# stm32-synthesizer_Schematic.net
KiCad netlist of a schematic drawn in Altium Designer
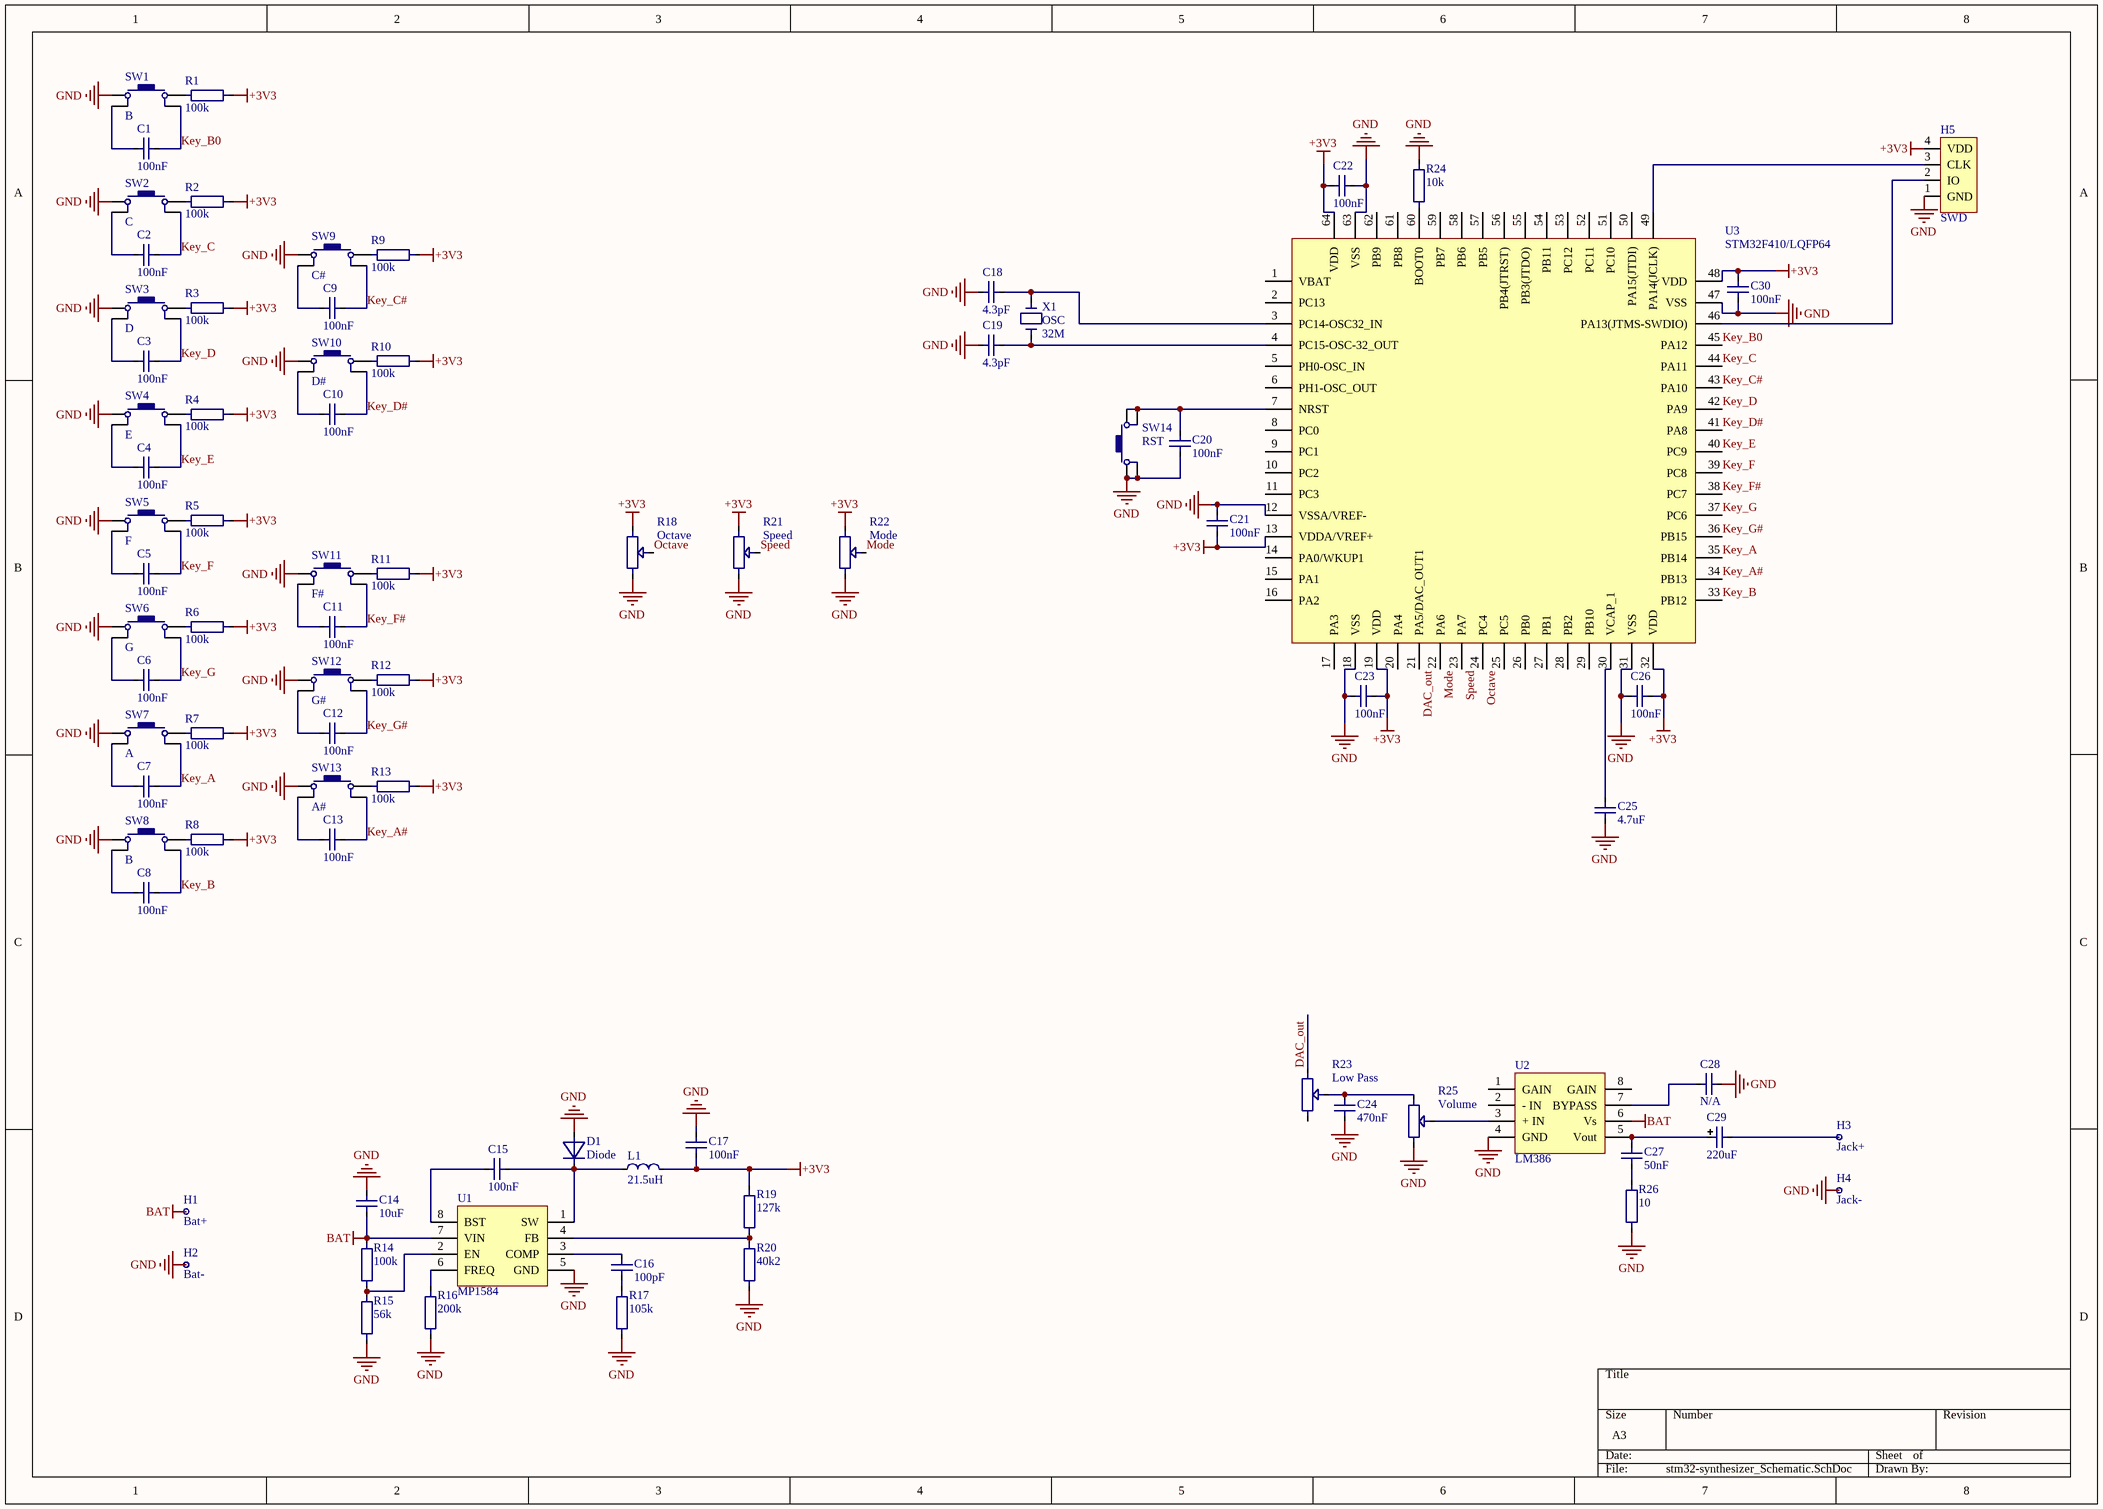
[diagram p0: stm32-synthesizer_Schematic.SchDoc]

(export (version "E")
  (design (tool "Eeschema 10.0.6"))
  (components
    (comp (ref "C1")
      (value "100nF")
      (footprint "CRCW0805")
      (libsource (lib "Schematic_Library_Warga") (part "Capacitor"))
    )
    (comp (ref "C2")
      (value "100nF")
      (footprint "CRCW0805")
      (libsource (lib "Schematic_Library_Warga") (part "Capacitor"))
    )
    (comp (ref "C3")
      (value "100nF")
      (footprint "CRCW0805")
      (libsource (lib "Schematic_Library_Warga") (part "Capacitor"))
    )
    (comp (ref "C4")
      (value "100nF")
      (footprint "CRCW0805")
      (libsource (lib "Schematic_Library_Warga") (part "Capacitor"))
    )
    (comp (ref "C5")
      (value "100nF")
      (footprint "CRCW0805")
      (libsource (lib "Schematic_Library_Warga") (part "Capacitor"))
    )
    (comp (ref "C6")
      (value "100nF")
      (footprint "CRCW0805")
      (libsource (lib "Schematic_Library_Warga") (part "Capacitor"))
    )
    (comp (ref "C7")
      (value "100nF")
      (footprint "CRCW0805")
      (libsource (lib "Schematic_Library_Warga") (part "Capacitor"))
    )
    (comp (ref "C8")
      (value "100nF")
      (footprint "CRCW0805")
      (libsource (lib "Schematic_Library_Warga") (part "Capacitor"))
    )
    (comp (ref "C9")
      (value "100nF")
      (footprint "CRCW0805")
      (libsource (lib "Schematic_Library_Warga") (part "Capacitor"))
    )
    (comp (ref "C10")
      (value "100nF")
      (footprint "CRCW0805")
      (libsource (lib "Schematic_Library_Warga") (part "Capacitor"))
    )
    (comp (ref "C11")
      (value "100nF")
      (footprint "CRCW0805")
      (libsource (lib "Schematic_Library_Warga") (part "Capacitor"))
    )
    (comp (ref "C12")
      (value "100nF")
      (footprint "CRCW0805")
      (libsource (lib "Schematic_Library_Warga") (part "Capacitor"))
    )
    (comp (ref "C13")
      (value "100nF")
      (footprint "CRCW0805")
      (libsource (lib "Schematic_Library_Warga") (part "Capacitor"))
    )
    (comp (ref "C14")
      (value "10uF")
      (footprint "CRCW0805")
      (libsource (lib "Schematic_Library_Warga") (part "Capacitor"))
    )
    (comp (ref "C15")
      (value "100nF")
      (footprint "GRM188")
      (libsource (lib "Schematic_Library_Warga") (part "Capacitor"))
    )
    (comp (ref "C16")
      (value "100pF")
      (footprint "CRCW0805")
      (libsource (lib "Schematic_Library_Warga") (part "Capacitor"))
    )
    (comp (ref "C17")
      (value "100nF")
      (footprint "GRM188")
      (libsource (lib "Schematic_Library_Warga") (part "Capacitor"))
    )
    (comp (ref "C18")
      (value "4.3pF")
      (footprint "CRCW0805")
      (libsource (lib "Schematic_Library_Warga") (part "Capacitor"))
    )
    (comp (ref "C19")
      (value "4.3pF")
      (footprint "CRCW0805")
      (libsource (lib "Schematic_Library_Warga") (part "Capacitor"))
    )
    (comp (ref "C20")
      (value "100nF")
      (footprint "CRCW0805")
      (libsource (lib "Schematic_Library_Warga") (part "Capacitor"))
    )
    (comp (ref "C21")
      (value "100nF")
      (footprint "CRCW0805")
      (libsource (lib "Schematic_Library_Warga") (part "Capacitor"))
    )
    (comp (ref "C22")
      (value "100nF")
      (footprint "CRCW0805")
      (libsource (lib "Schematic_Library_Warga") (part "Capacitor"))
    )
    (comp (ref "C23")
      (value "100nF")
      (footprint "CRCW0805")
      (libsource (lib "Schematic_Library_Warga") (part "Capacitor"))
    )
    (comp (ref "C24")
      (value "470nF")
      (footprint "CRCW0805")
      (libsource (lib "Schematic_Library_Warga") (part "Capacitor"))
    )
    (comp (ref "C25")
      (value "4.7uF")
      (footprint "CRCW0805")
      (libsource (lib "Schematic_Library_Warga") (part "Capacitor"))
    )
    (comp (ref "C26")
      (value "100nF")
      (footprint "CRCW0805")
      (libsource (lib "Schematic_Library_Warga") (part "Capacitor"))
    )
    (comp (ref "C27")
      (value "50nF")
      (footprint "CRCW0805")
      (libsource (lib "Schematic_Library_Warga") (part "Capacitor"))
    )
    (comp (ref "C28")
      (value "N/A")
      (footprint "CRCW0805")
      (libsource (lib "Schematic_Library_Warga") (part "Capacitor"))
    )
    (comp (ref "C29")
      (value "220uF")
      (footprint "CAPAE6766X81M")
      (libsource (lib "Schematic_Library_Warga") (part "Capacitor_Polarized"))
    )
    (comp (ref "C30")
      (value "100nF")
      (footprint "CRCW0805")
      (libsource (lib "Schematic_Library_Warga") (part "Capacitor"))
    )
    (comp (ref "D1")
      (value "Diode")
      (footprint "DIODES-INCORPORATED_1N5819")
      (libsource (lib "Schematic_Library_Warga") (part "Diode"))
    )
    (comp (ref "H1")
      (value "Bat+")
      (footprint "Hole 1mm")
      (libsource (lib "Schematic_Library_Warga") (part "Cable Hole"))
    )
    (comp (ref "H2")
      (value "Bat-")
      (footprint "Hole 1mm")
      (libsource (lib "Schematic_Library_Warga") (part "Cable Hole"))
    )
    (comp (ref "H3")
      (value "Jack+")
      (footprint "Hole 1mm")
      (libsource (lib "Schematic_Library_Warga") (part "Cable Hole"))
    )
    (comp (ref "H4")
      (value "Jack-")
      (footprint "Hole 1mm")
      (libsource (lib "Schematic_Library_Warga") (part "Cable Hole"))
    )
    (comp (ref "H5")
      (value "SWD")
      (footprint "M20-97704")
      (libsource (lib "Schematic_Library_Warga") (part "Header4"))
    )
    (comp (ref "L1")
      (value "21.5uH")
      (footprint "Coil 0.7mm d=7mm")
      (libsource (lib "Schematic_Library_Warga") (part "Coil"))
    )
    (comp (ref "R1")
      (value "100k")
      (footprint "CRCW0805")
      (libsource (lib "Schematic_Library_Warga") (part "Resitor"))
    )
    (comp (ref "R2")
      (value "100k")
      (footprint "CRCW0805")
      (libsource (lib "Schematic_Library_Warga") (part "Resitor"))
    )
    (comp (ref "R3")
      (value "100k")
      (footprint "CRCW0805")
      (libsource (lib "Schematic_Library_Warga") (part "Resitor"))
    )
    (comp (ref "R4")
      (value "100k")
      (footprint "CRCW0805")
      (libsource (lib "Schematic_Library_Warga") (part "Resitor"))
    )
    (comp (ref "R5")
      (value "100k")
      (footprint "CRCW0805")
      (libsource (lib "Schematic_Library_Warga") (part "Resitor"))
    )
    (comp (ref "R6")
      (value "100k")
      (footprint "CRCW0805")
      (libsource (lib "Schematic_Library_Warga") (part "Resitor"))
    )
    (comp (ref "R7")
      (value "100k")
      (footprint "CRCW0805")
      (libsource (lib "Schematic_Library_Warga") (part "Resitor"))
    )
    (comp (ref "R8")
      (value "100k")
      (footprint "CRCW0805")
      (libsource (lib "Schematic_Library_Warga") (part "Resitor"))
    )
    (comp (ref "R9")
      (value "100k")
      (footprint "CRCW0805")
      (libsource (lib "Schematic_Library_Warga") (part "Resitor"))
    )
    (comp (ref "R10")
      (value "100k")
      (footprint "CRCW0805")
      (libsource (lib "Schematic_Library_Warga") (part "Resitor"))
    )
    (comp (ref "R11")
      (value "100k")
      (footprint "CRCW0805")
      (libsource (lib "Schematic_Library_Warga") (part "Resitor"))
    )
    (comp (ref "R12")
      (value "100k")
      (footprint "CRCW0805")
      (libsource (lib "Schematic_Library_Warga") (part "Resitor"))
    )
    (comp (ref "R13")
      (value "100k")
      (footprint "CRCW0805")
      (libsource (lib "Schematic_Library_Warga") (part "Resitor"))
    )
    (comp (ref "R14")
      (value "100k")
      (footprint "CRCW0805")
      (libsource (lib "Schematic_Library_Warga") (part "Resitor"))
    )
    (comp (ref "R15")
      (value "56k")
      (footprint "CRCW0805")
      (libsource (lib "Schematic_Library_Warga") (part "Resitor"))
    )
    (comp (ref "R16")
      (value "200k")
      (footprint "CRCW0805")
      (libsource (lib "Schematic_Library_Warga") (part "Resitor"))
    )
    (comp (ref "R17")
      (value "105k")
      (footprint "CRCW0805")
      (libsource (lib "Schematic_Library_Warga") (part "Resitor"))
    )
    (comp (ref "R18")
      (value "Octave")
      (footprint "RK09K113")
      (libsource (lib "Schematic_Library_Warga") (part "Potentiometer"))
    )
    (comp (ref "R19")
      (value "127k")
      (footprint "CRCW0805")
      (libsource (lib "Schematic_Library_Warga") (part "Resitor"))
    )
    (comp (ref "R20")
      (value "40k2")
      (footprint "CRCW0805")
      (libsource (lib "Schematic_Library_Warga") (part "Resitor"))
    )
    (comp (ref "R21")
      (value "Speed")
      (footprint "RK09K113")
      (libsource (lib "Schematic_Library_Warga") (part "Potentiometer"))
    )
    (comp (ref "R22")
      (value "Mode")
      (footprint "RK09K113")
      (libsource (lib "Schematic_Library_Warga") (part "Potentiometer"))
    )
    (comp (ref "R23")
      (value "Low Pass")
      (footprint "RK09K113")
      (libsource (lib "Schematic_Library_Warga") (part "Potentiometer"))
    )
    (comp (ref "R24")
      (value "10k")
      (footprint "CRCW0805")
      (libsource (lib "Schematic_Library_Warga") (part "Resitor"))
    )
    (comp (ref "R25")
      (value "Volume")
      (footprint "RK09K113")
      (libsource (lib "Schematic_Library_Warga") (part "Potentiometer"))
    )
    (comp (ref "R26")
      (value "10")
      (footprint "CRCW0805")
      (libsource (lib "Schematic_Library_Warga") (part "Resitor"))
    )
    (comp (ref "SW1")
      (value "B")
      (footprint "TL1105")
      (libsource (lib "Schematic_Library_Warga") (part "Button"))
    )
    (comp (ref "SW2")
      (value "C")
      (footprint "TL1105")
      (libsource (lib "Schematic_Library_Warga") (part "Button"))
    )
    (comp (ref "SW3")
      (value "D")
      (footprint "TL1105")
      (libsource (lib "Schematic_Library_Warga") (part "Button"))
    )
    (comp (ref "SW4")
      (value "E")
      (footprint "TL1105")
      (libsource (lib "Schematic_Library_Warga") (part "Button"))
    )
    (comp (ref "SW5")
      (value "F")
      (footprint "TL1105")
      (libsource (lib "Schematic_Library_Warga") (part "Button"))
    )
    (comp (ref "SW6")
      (value "G")
      (footprint "TL1105")
      (libsource (lib "Schematic_Library_Warga") (part "Button"))
    )
    (comp (ref "SW7")
      (value "A")
      (footprint "TL1105")
      (libsource (lib "Schematic_Library_Warga") (part "Button"))
    )
    (comp (ref "SW8")
      (value "B")
      (footprint "TL1105")
      (libsource (lib "Schematic_Library_Warga") (part "Button"))
    )
    (comp (ref "SW9")
      (value "C#")
      (footprint "TL1105")
      (libsource (lib "Schematic_Library_Warga") (part "Button"))
    )
    (comp (ref "SW10")
      (value "D#")
      (footprint "TL1105")
      (libsource (lib "Schematic_Library_Warga") (part "Button"))
    )
    (comp (ref "SW11")
      (value "F#")
      (footprint "TL1105")
      (libsource (lib "Schematic_Library_Warga") (part "Button"))
    )
    (comp (ref "SW12")
      (value "G#")
      (footprint "TL1105")
      (libsource (lib "Schematic_Library_Warga") (part "Button"))
    )
    (comp (ref "SW13")
      (value "A#")
      (footprint "TL1105")
      (libsource (lib "Schematic_Library_Warga") (part "Button"))
    )
    (comp (ref "SW14") (value "RST") (footprint "TL1105") (libsource (lib "") (part "Button_1")))
    (comp (ref "U1")
      (value "MP1584")
      (footprint "SOIC127P600X175-8N")
      (libsource (lib "Schematic_Library_Warga") (part "MP1584"))
    )
    (comp (ref "U2")
      (value "LM386")
      (footprint "LM358 SOIC")
      (description "Low Voltage Audio Power Amplifier")
      (libsource (lib "Schematic_Library_Warga") (part "LM386"))
    )
    (comp (ref "U3")
      (value "STM32F410/LQFP64")
      (footprint "STM32F410/LQFP64")
      (libsource (lib "Schematic_Library_Warga") (part "STM32F410/LQFP64"))
    )
    (comp (ref "X1")
      (value "OSC")
      (footprint "SODFL1230X430-2N")
      (fields (field (name "FREQUENCY") "32M"))
      (libsource (lib "Schematic_Library_Warga") (part "Oscillator"))
    )
  )
  (nets
    (net (code "1") (name "+3V3") (class "Default")
      (node (ref "C17") (pin "1") (pinfunction "1_1") (pintype "passive"))
      (node (ref "C21") (pin "1") (pinfunction "1_1") (pintype "passive"))
      (node (ref "C22") (pin "1") (pinfunction "1_1") (pintype "passive"))
      (node (ref "C23") (pin "1") (pinfunction "1_1") (pintype "passive"))
      (node (ref "C26") (pin "1") (pinfunction "1_1") (pintype "passive"))
      (node (ref "C30") (pin "1") (pinfunction "1_1") (pintype "passive"))
      (node (ref "H5") (pin "4") (pinfunction "VDD_4") (pintype "passive"))
      (node (ref "L1") (pin "2") (pinfunction "2_2") (pintype "passive"))
      (node (ref "R1") (pin "2") (pinfunction "2_2") (pintype "passive"))
      (node (ref "R10") (pin "2") (pinfunction "2_2") (pintype "passive"))
      (node (ref "R11") (pin "2") (pinfunction "2_2") (pintype "passive"))
      (node (ref "R12") (pin "2") (pinfunction "2_2") (pintype "passive"))
      (node (ref "R13") (pin "2") (pinfunction "2_2") (pintype "passive"))
      (node (ref "R18") (pin "1") (pinfunction "1_1") (pintype "passive"))
      (node (ref "R19") (pin "2") (pinfunction "2_2") (pintype "passive"))
      (node (ref "R2") (pin "2") (pinfunction "2_2") (pintype "passive"))
      (node (ref "R21") (pin "1") (pinfunction "1_1") (pintype "passive"))
      (node (ref "R22") (pin "1") (pinfunction "1_1") (pintype "passive"))
      (node (ref "R3") (pin "2") (pinfunction "2_2") (pintype "passive"))
      (node (ref "R4") (pin "2") (pinfunction "2_2") (pintype "passive"))
      (node (ref "R5") (pin "2") (pinfunction "2_2") (pintype "passive"))
      (node (ref "R6") (pin "2") (pinfunction "2_2") (pintype "passive"))
      (node (ref "R7") (pin "2") (pinfunction "2_2") (pintype "passive"))
      (node (ref "R8") (pin "2") (pinfunction "2_2") (pintype "passive"))
      (node (ref "R9") (pin "2") (pinfunction "2_2") (pintype "passive"))
      (node (ref "U3") (pin "13") (pinfunction "VDDA/VREF+_13") (pintype "passive"))
      (node (ref "U3") (pin "19") (pinfunction "VDD_19") (pintype "passive"))
      (node (ref "U3") (pin "32") (pinfunction "VDD_32") (pintype "passive"))
      (node (ref "U3") (pin "48") (pinfunction "VDD_48") (pintype "passive"))
      (node (ref "U3") (pin "64") (pinfunction "VDD_64") (pintype "passive"))
    )
    (net (code "2") (name "/DAC_out") (class "Default")
      (node (ref "R23") (pin "1") (pinfunction "1_1") (pintype "passive"))
      (node (ref "U3") (pin "21") (pinfunction "PA5/DAC_OUT1_21") (pintype "passive"))
    )
    (net (code "3") (name "/Key_A") (class "Default")
      (node (ref "C7") (pin "2") (pinfunction "2_2") (pintype "passive"))
      (node (ref "SW7") (pin "4") (pinfunction "4_4") (pintype "passive"))
      (node (ref "U3") (pin "35") (pinfunction "PB14_35") (pintype "passive"))
    )
    (net (code "4") (name "/Key_A#") (class "Default")
      (node (ref "C13") (pin "2") (pinfunction "2_2") (pintype "passive"))
      (node (ref "SW13") (pin "4") (pinfunction "4_4") (pintype "passive"))
      (node (ref "U3") (pin "34") (pinfunction "PB13_34") (pintype "passive"))
    )
    (net (code "5") (name "/Key_B") (class "Default")
      (node (ref "C8") (pin "2") (pinfunction "2_2") (pintype "passive"))
      (node (ref "SW8") (pin "4") (pinfunction "4_4") (pintype "passive"))
      (node (ref "U3") (pin "33") (pinfunction "PB12_33") (pintype "passive"))
    )
    (net (code "6") (name "/Key_B0") (class "Default")
      (node (ref "C1") (pin "2") (pinfunction "2_2") (pintype "passive"))
      (node (ref "SW1") (pin "4") (pinfunction "4_4") (pintype "passive"))
      (node (ref "U3") (pin "45") (pinfunction "PA12_45") (pintype "passive"))
    )
    (net (code "7") (name "/Key_C") (class "Default")
      (node (ref "C2") (pin "2") (pinfunction "2_2") (pintype "passive"))
      (node (ref "SW2") (pin "4") (pinfunction "4_4") (pintype "passive"))
      (node (ref "U3") (pin "44") (pinfunction "PA11_44") (pintype "passive"))
    )
    (net (code "8") (name "/Key_C#") (class "Default")
      (node (ref "C9") (pin "2") (pinfunction "2_2") (pintype "passive"))
      (node (ref "SW9") (pin "4") (pinfunction "4_4") (pintype "passive"))
      (node (ref "U3") (pin "43") (pinfunction "PA10_43") (pintype "passive"))
    )
    (net (code "9") (name "/Key_D") (class "Default")
      (node (ref "C3") (pin "2") (pinfunction "2_2") (pintype "passive"))
      (node (ref "SW3") (pin "4") (pinfunction "4_4") (pintype "passive"))
      (node (ref "U3") (pin "42") (pinfunction "PA9_42") (pintype "passive"))
    )
    (net (code "10") (name "/Key_D#") (class "Default")
      (node (ref "C10") (pin "2") (pinfunction "2_2") (pintype "passive"))
      (node (ref "SW10") (pin "4") (pinfunction "4_4") (pintype "passive"))
      (node (ref "U3") (pin "41") (pinfunction "PA8_41") (pintype "passive"))
    )
    (net (code "11") (name "/Key_E") (class "Default")
      (node (ref "C4") (pin "2") (pinfunction "2_2") (pintype "passive"))
      (node (ref "SW4") (pin "4") (pinfunction "4_4") (pintype "passive"))
      (node (ref "U3") (pin "40") (pinfunction "PC9_40") (pintype "passive"))
    )
    (net (code "12") (name "/Key_F") (class "Default")
      (node (ref "C5") (pin "2") (pinfunction "2_2") (pintype "passive"))
      (node (ref "SW5") (pin "4") (pinfunction "4_4") (pintype "passive"))
      (node (ref "U3") (pin "39") (pinfunction "PC8_39") (pintype "passive"))
    )
    (net (code "13") (name "/Key_F#") (class "Default")
      (node (ref "C11") (pin "2") (pinfunction "2_2") (pintype "passive"))
      (node (ref "SW11") (pin "4") (pinfunction "4_4") (pintype "passive"))
      (node (ref "U3") (pin "38") (pinfunction "PC7_38") (pintype "passive"))
    )
    (net (code "14") (name "/Key_G") (class "Default")
      (node (ref "C6") (pin "2") (pinfunction "2_2") (pintype "passive"))
      (node (ref "SW6") (pin "4") (pinfunction "4_4") (pintype "passive"))
      (node (ref "U3") (pin "37") (pinfunction "PC6_37") (pintype "passive"))
    )
    (net (code "15") (name "/Key_G#") (class "Default")
      (node (ref "C12") (pin "2") (pinfunction "2_2") (pintype "passive"))
      (node (ref "SW12") (pin "4") (pinfunction "4_4") (pintype "passive"))
      (node (ref "U3") (pin "36") (pinfunction "PB15_36") (pintype "passive"))
    )
    (net (code "16") (name "/Mode") (class "Default")
      (node (ref "R22") (pin "2") (pinfunction "2_2") (pintype "passive"))
      (node (ref "U3") (pin "22") (pinfunction "PA6_22") (pintype "passive"))
    )
    (net (code "17") (name "/Octave") (class "Default")
      (node (ref "R18") (pin "2") (pinfunction "2_2") (pintype "passive"))
      (node (ref "U3") (pin "24") (pinfunction "PC4_24") (pintype "passive"))
    )
    (net (code "18") (name "/Speed") (class "Default")
      (node (ref "R21") (pin "2") (pinfunction "2_2") (pintype "passive"))
      (node (ref "U3") (pin "23") (pinfunction "PA7_23") (pintype "passive"))
    )
    (net (code "19") (name "BAT") (class "Default")
      (node (ref "C14") (pin "1") (pinfunction "1_1") (pintype "passive"))
      (node (ref "H1") (pin "1") (pinfunction "1_1") (pintype "passive"))
      (node (ref "R14") (pin "2") (pinfunction "2_2") (pintype "passive"))
      (node (ref "U1") (pin "7") (pinfunction "VIN_7") (pintype "passive"))
      (node (ref "U2") (pin "6") (pinfunction "Vs_6") (pintype "passive"))
    )
    (net (code "20") (name "GND") (class "Default")
      (node (ref "C14") (pin "2") (pinfunction "2_2") (pintype "passive"))
      (node (ref "C17") (pin "2") (pinfunction "2_2") (pintype "passive"))
      (node (ref "C18") (pin "2") (pinfunction "2_2") (pintype "passive"))
      (node (ref "C19") (pin "2") (pinfunction "2_2") (pintype "passive"))
      (node (ref "C20") (pin "1") (pinfunction "1_1") (pintype "passive"))
      (node (ref "C21") (pin "2") (pinfunction "2_2") (pintype "passive"))
      (node (ref "C22") (pin "2") (pinfunction "2_2") (pintype "passive"))
      (node (ref "C23") (pin "2") (pinfunction "2_2") (pintype "passive"))
      (node (ref "C24") (pin "1") (pinfunction "1_1") (pintype "passive"))
      (node (ref "C25") (pin "1") (pinfunction "1_1") (pintype "passive"))
      (node (ref "C26") (pin "2") (pinfunction "2_2") (pintype "passive"))
      (node (ref "C28") (pin "2") (pinfunction "2_2") (pintype "passive"))
      (node (ref "C30") (pin "2") (pinfunction "2_2") (pintype "passive"))
      (node (ref "D1") (pin "1") (pinfunction "1_1") (pintype "passive"))
      (node (ref "H2") (pin "1") (pinfunction "1_1") (pintype "passive"))
      (node (ref "H4") (pin "1") (pinfunction "1_1") (pintype "passive"))
      (node (ref "H5") (pin "1") (pinfunction "GND_1") (pintype "passive"))
      (node (ref "R15") (pin "1") (pinfunction "1_1") (pintype "passive"))
      (node (ref "R16") (pin "1") (pinfunction "1_1") (pintype "passive"))
      (node (ref "R17") (pin "1") (pinfunction "1_1") (pintype "passive"))
      (node (ref "R18") (pin "3") (pinfunction "3_3") (pintype "passive"))
      (node (ref "R20") (pin "1") (pinfunction "1_1") (pintype "passive"))
      (node (ref "R21") (pin "3") (pinfunction "3_3") (pintype "passive"))
      (node (ref "R22") (pin "3") (pinfunction "3_3") (pintype "passive"))
      (node (ref "R24") (pin "2") (pinfunction "2_2") (pintype "passive"))
      (node (ref "R25") (pin "3") (pinfunction "3_3") (pintype "passive"))
      (node (ref "R26") (pin "1") (pinfunction "1_1") (pintype "passive"))
      (node (ref "SW1") (pin "1") (pinfunction "1_1") (pintype "passive"))
      (node (ref "SW10") (pin "1") (pinfunction "1_1") (pintype "passive"))
      (node (ref "SW11") (pin "1") (pinfunction "1_1") (pintype "passive"))
      (node (ref "SW12") (pin "1") (pinfunction "1_1") (pintype "passive"))
      (node (ref "SW13") (pin "1") (pinfunction "1_1") (pintype "passive"))
      (node (ref "SW14") (pin "1") (pinfunction "1_1") (pintype "passive"))
      (node (ref "SW14") (pin "2") (pinfunction "2_2") (pintype "passive"))
      (node (ref "SW2") (pin "1") (pinfunction "1_1") (pintype "passive"))
      (node (ref "SW3") (pin "1") (pinfunction "1_1") (pintype "passive"))
      (node (ref "SW4") (pin "1") (pinfunction "1_1") (pintype "passive"))
      (node (ref "SW5") (pin "1") (pinfunction "1_1") (pintype "passive"))
      (node (ref "SW6") (pin "1") (pinfunction "1_1") (pintype "passive"))
      (node (ref "SW7") (pin "1") (pinfunction "1_1") (pintype "passive"))
      (node (ref "SW8") (pin "1") (pinfunction "1_1") (pintype "passive"))
      (node (ref "SW9") (pin "1") (pinfunction "1_1") (pintype "passive"))
      (node (ref "U1") (pin "5") (pinfunction "GND_5") (pintype "passive"))
      (node (ref "U2") (pin "4") (pinfunction "GND_4") (pintype "passive"))
      (node (ref "U3") (pin "12") (pinfunction "VSSA/VREF-_12") (pintype "passive"))
      (node (ref "U3") (pin "18") (pinfunction "VSS_18") (pintype "passive"))
      (node (ref "U3") (pin "31") (pinfunction "VSS_31") (pintype "passive"))
      (node (ref "U3") (pin "47") (pinfunction "VSS_47") (pintype "passive"))
      (node (ref "U3") (pin "63") (pinfunction "VSS_63") (pintype "passive"))
    )
    (net (code "21") (name "Net-(C1-Pad1)") (class "Default")
      (node (ref "C1") (pin "1") (pinfunction "1_1") (pintype "passive"))
      (node (ref "SW1") (pin "2") (pinfunction "2_2") (pintype "passive"))
    )
    (net (code "22") (name "Net-(C2-Pad1)") (class "Default")
      (node (ref "C2") (pin "1") (pinfunction "1_1") (pintype "passive"))
      (node (ref "SW2") (pin "2") (pinfunction "2_2") (pintype "passive"))
    )
    (net (code "23") (name "Net-(C3-Pad1)") (class "Default")
      (node (ref "C3") (pin "1") (pinfunction "1_1") (pintype "passive"))
      (node (ref "SW3") (pin "2") (pinfunction "2_2") (pintype "passive"))
    )
    (net (code "24") (name "Net-(C4-Pad1)") (class "Default")
      (node (ref "C4") (pin "1") (pinfunction "1_1") (pintype "passive"))
      (node (ref "SW4") (pin "2") (pinfunction "2_2") (pintype "passive"))
    )
    (net (code "25") (name "Net-(C5-Pad1)") (class "Default")
      (node (ref "C5") (pin "1") (pinfunction "1_1") (pintype "passive"))
      (node (ref "SW5") (pin "2") (pinfunction "2_2") (pintype "passive"))
    )
    (net (code "26") (name "Net-(C6-Pad1)") (class "Default")
      (node (ref "C6") (pin "1") (pinfunction "1_1") (pintype "passive"))
      (node (ref "SW6") (pin "2") (pinfunction "2_2") (pintype "passive"))
    )
    (net (code "27") (name "Net-(C7-Pad1)") (class "Default")
      (node (ref "C7") (pin "1") (pinfunction "1_1") (pintype "passive"))
      (node (ref "SW7") (pin "2") (pinfunction "2_2") (pintype "passive"))
    )
    (net (code "28") (name "Net-(C8-Pad1)") (class "Default")
      (node (ref "C8") (pin "1") (pinfunction "1_1") (pintype "passive"))
      (node (ref "SW8") (pin "2") (pinfunction "2_2") (pintype "passive"))
    )
    (net (code "29") (name "Net-(C9-Pad1)") (class "Default")
      (node (ref "C9") (pin "1") (pinfunction "1_1") (pintype "passive"))
      (node (ref "SW9") (pin "2") (pinfunction "2_2") (pintype "passive"))
    )
    (net (code "30") (name "Net-(C10-Pad1)") (class "Default")
      (node (ref "C10") (pin "1") (pinfunction "1_1") (pintype "passive"))
      (node (ref "SW10") (pin "2") (pinfunction "2_2") (pintype "passive"))
    )
    (net (code "31") (name "Net-(C11-Pad1)") (class "Default")
      (node (ref "C11") (pin "1") (pinfunction "1_1") (pintype "passive"))
      (node (ref "SW11") (pin "2") (pinfunction "2_2") (pintype "passive"))
    )
    (net (code "32") (name "Net-(C12-Pad1)") (class "Default")
      (node (ref "C12") (pin "1") (pinfunction "1_1") (pintype "passive"))
      (node (ref "SW12") (pin "2") (pinfunction "2_2") (pintype "passive"))
    )
    (net (code "33") (name "Net-(C13-Pad1)") (class "Default")
      (node (ref "C13") (pin "1") (pinfunction "1_1") (pintype "passive"))
      (node (ref "SW13") (pin "2") (pinfunction "2_2") (pintype "passive"))
    )
    (net (code "34") (name "Net-(C16-Pad1)") (class "Default")
      (node (ref "C16") (pin "1") (pinfunction "1_1") (pintype "passive"))
      (node (ref "R17") (pin "2") (pinfunction "2_2") (pintype "passive"))
    )
    (net (code "35") (name "Net-(C24-Pad2)") (class "Default")
      (node (ref "C24") (pin "2") (pinfunction "2_2") (pintype "passive"))
      (node (ref "R23") (pin "2") (pinfunction "2_2") (pintype "passive"))
      (node (ref "R25") (pin "1") (pinfunction "1_1") (pintype "passive"))
    )
    (net (code "36") (name "Net-(C27-Pad2)") (class "Default")
      (node (ref "C27") (pin "2") (pinfunction "2_2") (pintype "passive"))
      (node (ref "R26") (pin "2") (pinfunction "2_2") (pintype "passive"))
    )
    (net (code "37") (name "Net-(C29-Pad1)") (class "Default")
      (node (ref "C29") (pin "1") (pinfunction "1_1") (pintype "passive"))
      (node (ref "H3") (pin "1") (pinfunction "1_1") (pintype "passive"))
    )
    (net (code "38") (name "Net-(H5-CLK)") (class "Default")
      (node (ref "H5") (pin "3") (pinfunction "CLK_3") (pintype "passive"))
      (node (ref "U3") (pin "49") (pinfunction "PA14(JCLK)_49") (pintype "passive"))
    )
    (net (code "39") (name "Net-(H5-IO)") (class "Default")
      (node (ref "H5") (pin "2") (pinfunction "IO_2") (pintype "passive"))
      (node (ref "U3") (pin "46") (pinfunction "PA13(JTMS-SWDIO)_46") (pintype "passive"))
    )
    (net (code "40") (name "Net-(R1-Pad1)") (class "Default")
      (node (ref "R1") (pin "1") (pinfunction "1_1") (pintype "passive"))
      (node (ref "SW1") (pin "3") (pinfunction "3_3") (pintype "passive"))
    )
    (net (code "41") (name "Net-(R2-Pad1)") (class "Default")
      (node (ref "R2") (pin "1") (pinfunction "1_1") (pintype "passive"))
      (node (ref "SW2") (pin "3") (pinfunction "3_3") (pintype "passive"))
    )
    (net (code "42") (name "Net-(R3-Pad1)") (class "Default")
      (node (ref "R3") (pin "1") (pinfunction "1_1") (pintype "passive"))
      (node (ref "SW3") (pin "3") (pinfunction "3_3") (pintype "passive"))
    )
    (net (code "43") (name "Net-(R4-Pad1)") (class "Default")
      (node (ref "R4") (pin "1") (pinfunction "1_1") (pintype "passive"))
      (node (ref "SW4") (pin "3") (pinfunction "3_3") (pintype "passive"))
    )
    (net (code "44") (name "Net-(R5-Pad1)") (class "Default")
      (node (ref "R5") (pin "1") (pinfunction "1_1") (pintype "passive"))
      (node (ref "SW5") (pin "3") (pinfunction "3_3") (pintype "passive"))
    )
    (net (code "45") (name "Net-(R6-Pad1)") (class "Default")
      (node (ref "R6") (pin "1") (pinfunction "1_1") (pintype "passive"))
      (node (ref "SW6") (pin "3") (pinfunction "3_3") (pintype "passive"))
    )
    (net (code "46") (name "Net-(R7-Pad1)") (class "Default")
      (node (ref "R7") (pin "1") (pinfunction "1_1") (pintype "passive"))
      (node (ref "SW7") (pin "3") (pinfunction "3_3") (pintype "passive"))
    )
    (net (code "47") (name "Net-(R8-Pad1)") (class "Default")
      (node (ref "R8") (pin "1") (pinfunction "1_1") (pintype "passive"))
      (node (ref "SW8") (pin "3") (pinfunction "3_3") (pintype "passive"))
    )
    (net (code "48") (name "Net-(R9-Pad1)") (class "Default")
      (node (ref "R9") (pin "1") (pinfunction "1_1") (pintype "passive"))
      (node (ref "SW9") (pin "3") (pinfunction "3_3") (pintype "passive"))
    )
    (net (code "49") (name "Net-(R10-Pad1)") (class "Default")
      (node (ref "R10") (pin "1") (pinfunction "1_1") (pintype "passive"))
      (node (ref "SW10") (pin "3") (pinfunction "3_3") (pintype "passive"))
    )
    (net (code "50") (name "Net-(R11-Pad1)") (class "Default")
      (node (ref "R11") (pin "1") (pinfunction "1_1") (pintype "passive"))
      (node (ref "SW11") (pin "3") (pinfunction "3_3") (pintype "passive"))
    )
    (net (code "51") (name "Net-(R12-Pad1)") (class "Default")
      (node (ref "R12") (pin "1") (pinfunction "1_1") (pintype "passive"))
      (node (ref "SW12") (pin "3") (pinfunction "3_3") (pintype "passive"))
    )
    (net (code "52") (name "Net-(R13-Pad1)") (class "Default")
      (node (ref "R13") (pin "1") (pinfunction "1_1") (pintype "passive"))
      (node (ref "SW13") (pin "3") (pinfunction "3_3") (pintype "passive"))
    )
    (net (code "53") (name "Net-(U1-BST)") (class "Default")
      (node (ref "C15") (pin "1") (pinfunction "1_1") (pintype "passive"))
      (node (ref "U1") (pin "8") (pinfunction "BST_8") (pintype "passive"))
    )
    (net (code "54") (name "Net-(U1-COMP)") (class "Default")
      (node (ref "C16") (pin "2") (pinfunction "2_2") (pintype "passive"))
      (node (ref "U1") (pin "3") (pinfunction "COMP_3") (pintype "passive"))
    )
    (net (code "55") (name "Net-(U1-EN)") (class "Default")
      (node (ref "R14") (pin "1") (pinfunction "1_1") (pintype "passive"))
      (node (ref "R15") (pin "2") (pinfunction "2_2") (pintype "passive"))
      (node (ref "U1") (pin "2") (pinfunction "EN_2") (pintype "passive"))
    )
    (net (code "56") (name "Net-(U1-FB)") (class "Default")
      (node (ref "R19") (pin "1") (pinfunction "1_1") (pintype "passive"))
      (node (ref "R20") (pin "2") (pinfunction "2_2") (pintype "passive"))
      (node (ref "U1") (pin "4") (pinfunction "FB_4") (pintype "passive"))
    )
    (net (code "57") (name "Net-(U1-FREQ)") (class "Default")
      (node (ref "R16") (pin "2") (pinfunction "2_2") (pintype "passive"))
      (node (ref "U1") (pin "6") (pinfunction "FREQ_6") (pintype "passive"))
    )
    (net (code "58") (name "Net-(U1-SW)") (class "Default")
      (node (ref "C15") (pin "2") (pinfunction "2_2") (pintype "passive"))
      (node (ref "D1") (pin "2") (pinfunction "2_2") (pintype "passive"))
      (node (ref "L1") (pin "1") (pinfunction "1_1") (pintype "passive"))
      (node (ref "U1") (pin "1") (pinfunction "SW_1") (pintype "passive"))
    )
    (net (code "59") (name "Net-(U2-+_IN)") (class "Default")
      (node (ref "R25") (pin "2") (pinfunction "2_2") (pintype "passive"))
      (node (ref "U2") (pin "3") (pinfunction "+_IN_3") (pintype "passive"))
    )
    (net (code "60") (name "Net-(U2-BYPASS)") (class "Default")
      (node (ref "C28") (pin "1") (pinfunction "1_1") (pintype "passive"))
      (node (ref "U2") (pin "7") (pinfunction "BYPASS_7") (pintype "passive"))
    )
    (net (code "61") (name "Net-(U2-Vout)") (class "Default")
      (node (ref "C27") (pin "1") (pinfunction "1_1") (pintype "passive"))
      (node (ref "C29") (pin "2") (pinfunction "2_2") (pintype "passive"))
      (node (ref "U2") (pin "5") (pinfunction "Vout_5") (pintype "passive"))
    )
    (net (code "62") (name "Net-(U3-BOOT0)") (class "Default")
      (node (ref "R24") (pin "1") (pinfunction "1_1") (pintype "passive"))
      (node (ref "U3") (pin "60") (pinfunction "BOOT0_60") (pintype "passive"))
    )
    (net (code "63") (name "Net-(U3-NRST)") (class "Default")
      (node (ref "C20") (pin "2") (pinfunction "2_2") (pintype "passive"))
      (node (ref "SW14") (pin "3") (pinfunction "3_3") (pintype "passive"))
      (node (ref "SW14") (pin "4") (pinfunction "4_4") (pintype "passive"))
      (node (ref "U3") (pin "7") (pinfunction "NRST_7") (pintype "passive"))
    )
    (net (code "64") (name "Net-(U3-PC14-OSC32_IN)") (class "Default")
      (node (ref "C18") (pin "1") (pinfunction "1_1") (pintype "passive"))
      (node (ref "U3") (pin "3") (pinfunction "PC14-OSC32_IN_3") (pintype "passive"))
      (node (ref "X1") (pin "2") (pinfunction "2_2") (pintype "passive"))
    )
    (net (code "65") (name "Net-(U3-PC15-OSC-32_OUT)") (class "Default")
      (node (ref "C19") (pin "1") (pinfunction "1_1") (pintype "passive"))
      (node (ref "U3") (pin "4") (pinfunction "PC15-OSC-32_OUT_4") (pintype "passive"))
      (node (ref "X1") (pin "1") (pinfunction "1_1") (pintype "passive"))
    )
    (net (code "66") (name "Net-(U3-VCAP_1)") (class "Default")
      (node (ref "C25") (pin "2") (pinfunction "2_2") (pintype "passive"))
      (node (ref "U3") (pin "30") (pinfunction "VCAP_1_30") (pintype "passive"))
    )
    (net (code "67") (name "unconnected-(R23-Pad3)") (class "Default")
      (node (ref "R23") (pin "3") (pinfunction "3_3") (pintype "passive"))
    )
    (net (code "68") (name "unconnected-(U2--_IN-Pad2)") (class "Default")
      (node (ref "U2") (pin "2") (pinfunction "-_IN_2") (pintype "passive"))
    )
    (net (code "69") (name "unconnected-(U2-GAIN-Pad1)") (class "Default")
      (node (ref "U2") (pin "1") (pinfunction "GAIN_1") (pintype "passive"))
    )
    (net (code "70") (name "unconnected-(U2-GAIN-Pad8)") (class "Default")
      (node (ref "U2") (pin "8") (pinfunction "GAIN_8") (pintype "passive"))
    )
    (net (code "71") (name "unconnected-(U3-PA0{slash}WKUP1-Pad14)") (class "Default")
      (node (ref "U3") (pin "14") (pinfunction "PA0/WKUP1_14") (pintype "passive"))
    )
    (net (code "72") (name "unconnected-(U3-PA1-Pad15)") (class "Default")
      (node (ref "U3") (pin "15") (pinfunction "PA1_15") (pintype "passive"))
    )
    (net (code "73") (name "unconnected-(U3-PA2-Pad16)") (class "Default")
      (node (ref "U3") (pin "16") (pinfunction "PA2_16") (pintype "passive"))
    )
    (net (code "74") (name "unconnected-(U3-PA3-Pad17)") (class "Default")
      (node (ref "U3") (pin "17") (pinfunction "PA3_17") (pintype "passive"))
    )
    (net (code "75") (name "unconnected-(U3-PA4-Pad20)") (class "Default")
      (node (ref "U3") (pin "20") (pinfunction "PA4_20") (pintype "passive"))
    )
    (net (code "76") (name "unconnected-(U3-PA15(JTDI)-Pad50)") (class "Default")
      (node (ref "U3") (pin "50") (pinfunction "PA15(JTDI)_50") (pintype "passive"))
    )
    (net (code "77") (name "unconnected-(U3-PB0-Pad26)") (class "Default")
      (node (ref "U3") (pin "26") (pinfunction "PB0_26") (pintype "passive"))
    )
    (net (code "78") (name "unconnected-(U3-PB1-Pad27)") (class "Default")
      (node (ref "U3") (pin "27") (pinfunction "PB1_27") (pintype "passive"))
    )
    (net (code "79") (name "unconnected-(U3-PB2-Pad28)") (class "Default")
      (node (ref "U3") (pin "28") (pinfunction "PB2_28") (pintype "passive"))
    )
    (net (code "80") (name "unconnected-(U3-PB3(JTDO)-Pad55)") (class "Default")
      (node (ref "U3") (pin "55") (pinfunction "PB3(JTDO)_55") (pintype "passive"))
    )
    (net (code "81") (name "unconnected-(U3-PB4(JTRST)-Pad56)") (class "Default")
      (node (ref "U3") (pin "56") (pinfunction "PB4(JTRST)_56") (pintype "passive"))
    )
    (net (code "82") (name "unconnected-(U3-PB5-Pad57)") (class "Default")
      (node (ref "U3") (pin "57") (pinfunction "PB5_57") (pintype "passive"))
    )
    (net (code "83") (name "unconnected-(U3-PB6-Pad58)") (class "Default")
      (node (ref "U3") (pin "58") (pinfunction "PB6_58") (pintype "passive"))
    )
    (net (code "84") (name "unconnected-(U3-PB7-Pad59)") (class "Default")
      (node (ref "U3") (pin "59") (pinfunction "PB7_59") (pintype "passive"))
    )
    (net (code "85") (name "unconnected-(U3-PB8-Pad61)") (class "Default")
      (node (ref "U3") (pin "61") (pinfunction "PB8_61") (pintype "passive"))
    )
    (net (code "86") (name "unconnected-(U3-PB9-Pad62)") (class "Default")
      (node (ref "U3") (pin "62") (pinfunction "PB9_62") (pintype "passive"))
    )
    (net (code "87") (name "unconnected-(U3-PB10-Pad29)") (class "Default")
      (node (ref "U3") (pin "29") (pinfunction "PB10_29") (pintype "passive"))
    )
    (net (code "88") (name "unconnected-(U3-PB11-Pad54)") (class "Default")
      (node (ref "U3") (pin "54") (pinfunction "PB11_54") (pintype "passive"))
    )
    (net (code "89") (name "unconnected-(U3-PC0-Pad8)") (class "Default")
      (node (ref "U3") (pin "8") (pinfunction "PC0_8") (pintype "passive"))
    )
    (net (code "90") (name "unconnected-(U3-PC1-Pad9)") (class "Default")
      (node (ref "U3") (pin "9") (pinfunction "PC1_9") (pintype "passive"))
    )
    (net (code "91") (name "unconnected-(U3-PC2-Pad10)") (class "Default")
      (node (ref "U3") (pin "10") (pinfunction "PC2_10") (pintype "passive"))
    )
    (net (code "92") (name "unconnected-(U3-PC3-Pad11)") (class "Default")
      (node (ref "U3") (pin "11") (pinfunction "PC3_11") (pintype "passive"))
    )
    (net (code "93") (name "unconnected-(U3-PC5-Pad25)") (class "Default")
      (node (ref "U3") (pin "25") (pinfunction "PC5_25") (pintype "passive"))
    )
    (net (code "94") (name "unconnected-(U3-PC10-Pad51)") (class "Default")
      (node (ref "U3") (pin "51") (pinfunction "PC10_51") (pintype "passive"))
    )
    (net (code "95") (name "unconnected-(U3-PC11-Pad52)") (class "Default")
      (node (ref "U3") (pin "52") (pinfunction "PC11_52") (pintype "passive"))
    )
    (net (code "96") (name "unconnected-(U3-PC12-Pad53)") (class "Default")
      (node (ref "U3") (pin "53") (pinfunction "PC12_53") (pintype "passive"))
    )
    (net (code "97") (name "unconnected-(U3-PC13-Pad2)") (class "Default")
      (node (ref "U3") (pin "2") (pinfunction "PC13_2") (pintype "passive"))
    )
    (net (code "98") (name "unconnected-(U3-PH0-OSC_IN-Pad5)") (class "Default")
      (node (ref "U3") (pin "5") (pinfunction "PH0-OSC_IN_5") (pintype "passive"))
    )
    (net (code "99") (name "unconnected-(U3-PH1-OSC_OUT-Pad6)") (class "Default")
      (node (ref "U3") (pin "6") (pinfunction "PH1-OSC_OUT_6") (pintype "passive"))
    )
    (net (code "100") (name "unconnected-(U3-VBAT-Pad1)") (class "Default")
      (node (ref "U3") (pin "1") (pinfunction "VBAT_1") (pintype "passive"))
    )
  )
)
